# House_Illumination_Core.net
KiCad netlist of a schematic drawn in EAGLE
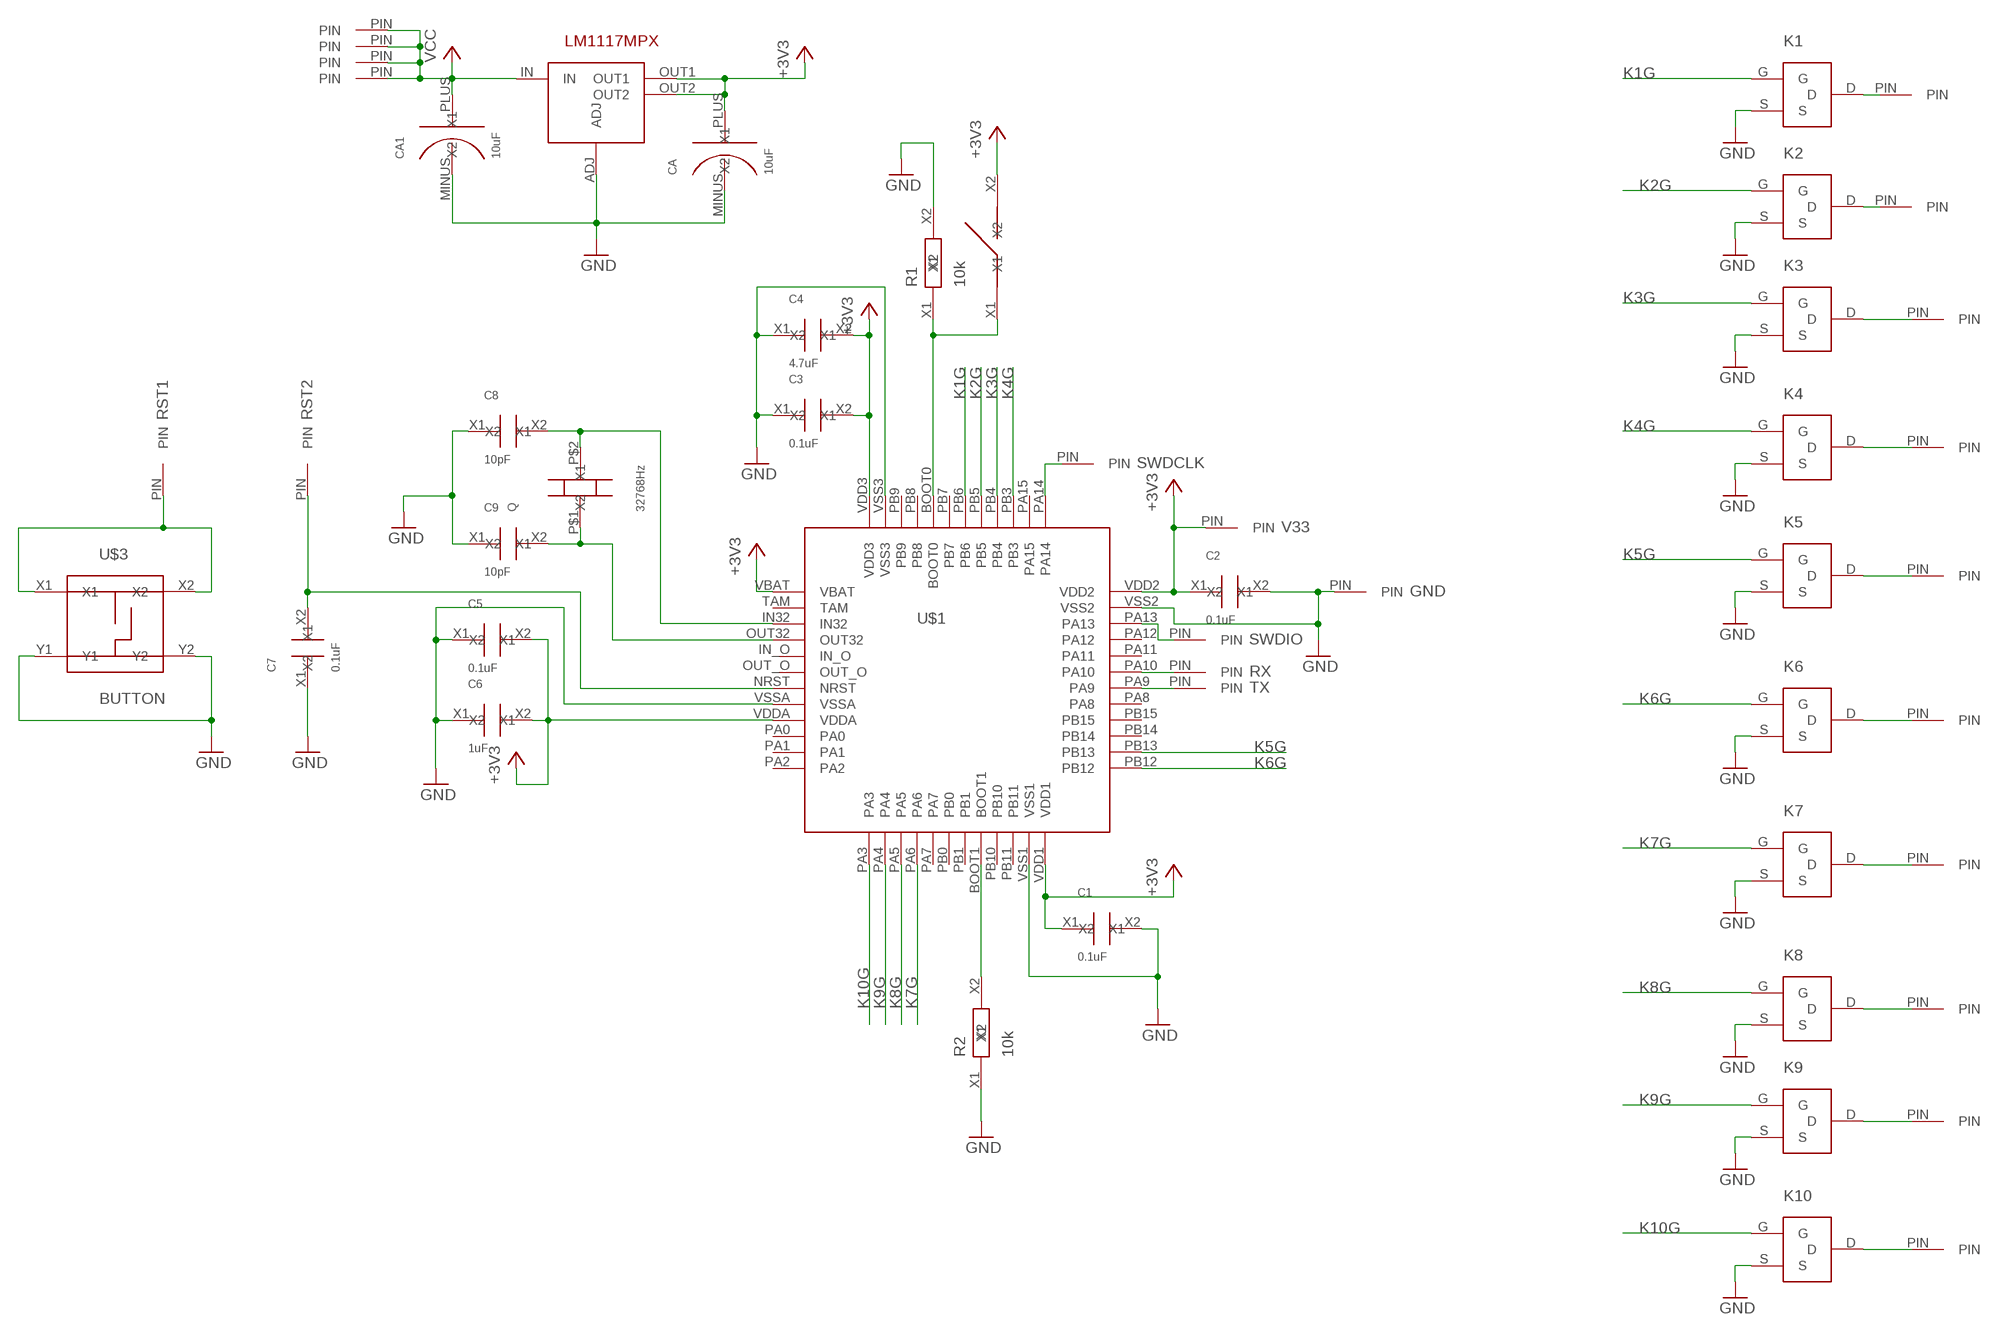
[diagram p0: schematic, sheet 1]

(export (version "E")
  (design (tool "Eeschema 10.0.6"))
  (components
    (comp (ref "C1")
      (value "0.1uF")
      (footprint "eagle-import:SMD_2.1X1.25")
      (libsource (lib "eagle-import") (part "C_SMD_2.1X1.25"))
    )
    (comp (ref "C2")
      (value "0.1uF")
      (footprint "eagle-import:SMD_2.1X1.25")
      (libsource (lib "eagle-import") (part "C_SMD_2.1X1.25"))
    )
    (comp (ref "C3")
      (value "0.1uF")
      (footprint "eagle-import:SMD_2.1X1.25")
      (libsource (lib "eagle-import") (part "C_SMD_2.1X1.25"))
    )
    (comp (ref "C4")
      (value "4.7uF")
      (footprint "eagle-import:SMD_2.1X1.25")
      (libsource (lib "eagle-import") (part "C_SMD_2.1X1.25"))
    )
    (comp (ref "C5")
      (value "0.1uF")
      (footprint "eagle-import:SMD_2.1X1.25")
      (libsource (lib "eagle-import") (part "C_SMD_2.1X1.25"))
    )
    (comp (ref "C6")
      (value "1uF")
      (footprint "eagle-import:SMD_2.1X1.25")
      (libsource (lib "eagle-import") (part "C_SMD_2.1X1.25"))
    )
    (comp (ref "C7")
      (value "0.1uF")
      (footprint "eagle-import:SMD_2.1X1.25")
      (libsource (lib "eagle-import") (part "C_SMD_2.1X1.25"))
    )
    (comp (ref "C8")
      (value "10pF")
      (footprint "eagle-import:SMD_2.1X1.25")
      (libsource (lib "eagle-import") (part "C_SMD_2.1X1.25"))
    )
    (comp (ref "C9")
      (value "10pF")
      (footprint "eagle-import:SMD_2.1X1.25")
      (libsource (lib "eagle-import") (part "C_SMD_2.1X1.25"))
    )
    (comp (ref "CA")
      (value "10uF")
      (footprint "eagle-import:C_SMD_TA_A")
      (libsource (lib "eagle-import") (part "C_SMD_TA_A"))
    )
    (comp (ref "CA1")
      (value "10uF")
      (footprint "eagle-import:C_SMD_TA_A")
      (libsource (lib "eagle-import") (part "C_SMD_TA_A"))
    )
    (comp (ref "GND")
      (value "PIN")
      (footprint "eagle-import:PIN")
      (libsource (lib "eagle-import") (part "PIN"))
    )
    (comp (ref "K1")
      (value "IRFML8244TRPBF")
      (footprint "eagle-import:IRFML8244TRPBF")
      (libsource (lib "eagle-import") (part "IRFML8244TRPBF"))
    )
    (comp (ref "K2")
      (value "IRFML8244TRPBF")
      (footprint "eagle-import:IRFML8244TRPBF")
      (libsource (lib "eagle-import") (part "IRFML8244TRPBF"))
    )
    (comp (ref "K3")
      (value "IRFML8244TRPBF")
      (footprint "eagle-import:IRFML8244TRPBF")
      (libsource (lib "eagle-import") (part "IRFML8244TRPBF"))
    )
    (comp (ref "K4")
      (value "IRFML8244TRPBF")
      (footprint "eagle-import:IRFML8244TRPBF")
      (libsource (lib "eagle-import") (part "IRFML8244TRPBF"))
    )
    (comp (ref "K5")
      (value "IRFML8244TRPBF")
      (footprint "eagle-import:IRFML8244TRPBF")
      (libsource (lib "eagle-import") (part "IRFML8244TRPBF"))
    )
    (comp (ref "K6")
      (value "IRFML8244TRPBF")
      (footprint "eagle-import:IRFML8244TRPBF")
      (libsource (lib "eagle-import") (part "IRFML8244TRPBF"))
    )
    (comp (ref "K7")
      (value "IRFML8244TRPBF")
      (footprint "eagle-import:IRFML8244TRPBF")
      (libsource (lib "eagle-import") (part "IRFML8244TRPBF"))
    )
    (comp (ref "K8")
      (value "IRFML8244TRPBF")
      (footprint "eagle-import:IRFML8244TRPBF")
      (libsource (lib "eagle-import") (part "IRFML8244TRPBF"))
    )
    (comp (ref "K9")
      (value "IRFML8244TRPBF")
      (footprint "eagle-import:IRFML8244TRPBF")
      (libsource (lib "eagle-import") (part "IRFML8244TRPBF"))
    )
    (comp (ref "K10")
      (value "IRFML8244TRPBF")
      (footprint "eagle-import:IRFML8244TRPBF")
      (libsource (lib "eagle-import") (part "IRFML8244TRPBF"))
    )
    (comp (ref "LED1")
      (value "PIN_1")
      (footprint "eagle-import:PIN_1")
      (libsource (lib "eagle-import") (part "PIN_1"))
    )
    (comp (ref "LED2")
      (value "PIN_1")
      (footprint "eagle-import:PIN_1")
      (libsource (lib "eagle-import") (part "PIN_1"))
    )
    (comp (ref "LED3")
      (value "PIN_1")
      (footprint "eagle-import:PIN_1")
      (libsource (lib "eagle-import") (part "PIN_1"))
    )
    (comp (ref "LED4")
      (value "PIN_1")
      (footprint "eagle-import:PIN_1")
      (libsource (lib "eagle-import") (part "PIN_1"))
    )
    (comp (ref "LED5")
      (value "PIN_1")
      (footprint "eagle-import:PIN_1")
      (libsource (lib "eagle-import") (part "PIN_1"))
    )
    (comp (ref "LED6")
      (value "PIN_1")
      (footprint "eagle-import:PIN_1")
      (libsource (lib "eagle-import") (part "PIN_1"))
    )
    (comp (ref "LED7")
      (value "PIN_1")
      (footprint "eagle-import:PIN_1")
      (libsource (lib "eagle-import") (part "PIN_1"))
    )
    (comp (ref "LED8")
      (value "PIN_1")
      (footprint "eagle-import:PIN_1")
      (libsource (lib "eagle-import") (part "PIN_1"))
    )
    (comp (ref "LED9")
      (value "PIN_1")
      (footprint "eagle-import:PIN_1")
      (libsource (lib "eagle-import") (part "PIN_1"))
    )
    (comp (ref "LED10")
      (value "PIN_1")
      (footprint "eagle-import:PIN_1")
      (libsource (lib "eagle-import") (part "PIN_1"))
    )
    (comp (ref "Q")
      (value "32768Hz")
      (footprint "eagle-import:QUARTZ_CYL")
      (libsource (lib "eagle-import") (part "QUARTZ_CYL"))
    )
    (comp (ref "R1")
      (value "10k")
      (footprint "eagle-import:SMD_2.1X1.25")
      (libsource (lib "eagle-import") (part "R_SMD_2.1X1.25"))
    )
    (comp (ref "R2")
      (value "10k")
      (footprint "eagle-import:SMD_2.1X1.25")
      (libsource (lib "eagle-import") (part "R_SMD_2.1X1.25"))
    )
    (comp (ref "RST1")
      (value "PIN")
      (footprint "eagle-import:PIN")
      (libsource (lib "eagle-import") (part "PIN"))
    )
    (comp (ref "RST2")
      (value "PIN")
      (footprint "eagle-import:PIN")
      (libsource (lib "eagle-import") (part "PIN"))
    )
    (comp (ref "RX")
      (value "PIN")
      (footprint "eagle-import:PIN")
      (libsource (lib "eagle-import") (part "PIN"))
    )
    (comp (ref "SWDCLK")
      (value "PIN")
      (footprint "eagle-import:PIN")
      (libsource (lib "eagle-import") (part "PIN"))
    )
    (comp (ref "SWDIO")
      (value "PIN")
      (footprint "eagle-import:PIN")
      (libsource (lib "eagle-import") (part "PIN"))
    )
    (comp (ref "TX")
      (value "PIN")
      (footprint "eagle-import:PIN")
      (libsource (lib "eagle-import") (part "PIN"))
    )
    (comp (ref "U$1")
      (value "STM32F103CBT6")
      (footprint "eagle-import:STM32F103CBT6")
      (libsource (lib "eagle-import") (part "STM32F103CBT6"))
    )
    (comp (ref "U$2")
      (value "DIP_1")
      (footprint "eagle-import:DIP_1")
      (libsource (lib "eagle-import") (part "DIP_1"))
    )
    (comp (ref "U$3")
      (value "BUTTON")
      (footprint "eagle-import:BUTTON")
      (libsource (lib "eagle-import") (part "BUTTON"))
    )
    (comp (ref "U$13")
      (value "LM1117MPX-ADJ")
      (footprint "eagle-import:LM1117MPX-ADJ")
      (libsource (lib "eagle-import") (part "LM1117MPX-ADJ"))
    )
    (comp (ref "V33")
      (value "PIN")
      (footprint "eagle-import:PIN")
      (libsource (lib "eagle-import") (part "PIN"))
    )
    (comp (ref "VCCPIN")
      (value "PIN_1")
      (footprint "eagle-import:PIN_1")
      (libsource (lib "eagle-import") (part "PIN_1"))
    )
    (comp (ref "VCCPIN1")
      (value "PIN_1")
      (footprint "eagle-import:PIN_1")
      (libsource (lib "eagle-import") (part "PIN_1"))
    )
    (comp (ref "VCCPIN2")
      (value "PIN_1")
      (footprint "eagle-import:PIN_1")
      (libsource (lib "eagle-import") (part "PIN_1"))
    )
    (comp (ref "VCCPIN3")
      (value "PIN_1")
      (footprint "eagle-import:PIN_1")
      (libsource (lib "eagle-import") (part "PIN_1"))
    )
  )
  (nets
    (net (code "1") (name "+3V3") (class "Default")
      (node (ref "C1") (pin "X1") (pinfunction "X1_X1") (pintype "bidirectional"))
      (node (ref "C2") (pin "X1") (pinfunction "X1_X1") (pintype "bidirectional"))
      (node (ref "C3") (pin "X2") (pinfunction "X2_X2") (pintype "bidirectional"))
      (node (ref "C4") (pin "X2") (pinfunction "X2_X2") (pintype "bidirectional"))
      (node (ref "C5") (pin "X2") (pinfunction "X2_X2") (pintype "bidirectional"))
      (node (ref "C6") (pin "X2") (pinfunction "X2_X2") (pintype "bidirectional"))
      (node (ref "CA") (pin "PLUS") (pinfunction "X2_PLUS") (pintype "bidirectional"))
      (node (ref "U$1") (pin "VBAT") (pinfunction "VBAT_VBAT") (pintype "bidirectional"))
      (node (ref "U$1") (pin "VDD1") (pinfunction "VDD1_VDD1") (pintype "bidirectional"))
      (node (ref "U$1") (pin "VDD2") (pinfunction "VDD2_VDD2") (pintype "bidirectional"))
      (node (ref "U$1") (pin "VDD3") (pinfunction "VDD3_VDD3") (pintype "bidirectional"))
      (node (ref "U$1") (pin "VDDA") (pinfunction "VDDA_VDDA") (pintype "bidirectional"))
      (node (ref "U$13") (pin "OUT1") (pinfunction "OUT1_OUT1") (pintype "bidirectional"))
      (node (ref "U$13") (pin "OUT2") (pinfunction "OUT2_OUT2") (pintype "bidirectional"))
      (node (ref "U$2") (pin "X2") (pinfunction "X2_X2") (pintype "bidirectional"))
      (node (ref "V33") (pin "PIN") (pinfunction "PIN_PIN") (pintype "bidirectional"))
    )
    (net (code "2") (name "/K1G") (class "Default")
      (node (ref "K1") (pin "G") (pinfunction "G_G") (pintype "bidirectional"))
      (node (ref "U$1") (pin "PB6") (pinfunction "PB6_PB6") (pintype "bidirectional"))
    )
    (net (code "3") (name "/K2G") (class "Default")
      (node (ref "K2") (pin "G") (pinfunction "G_G") (pintype "bidirectional"))
      (node (ref "U$1") (pin "PB5") (pinfunction "PB5_PB5") (pintype "bidirectional"))
    )
    (net (code "4") (name "/K3G") (class "Default")
      (node (ref "K3") (pin "G") (pinfunction "G_G") (pintype "bidirectional"))
      (node (ref "U$1") (pin "PB4") (pinfunction "PB4_PB4") (pintype "bidirectional"))
    )
    (net (code "5") (name "/K4G") (class "Default")
      (node (ref "K4") (pin "G") (pinfunction "G_G") (pintype "bidirectional"))
      (node (ref "U$1") (pin "PB3") (pinfunction "PB3_PB3") (pintype "bidirectional"))
    )
    (net (code "6") (name "/K5G") (class "Default")
      (node (ref "K5") (pin "G") (pinfunction "G_G") (pintype "bidirectional"))
      (node (ref "U$1") (pin "PB13") (pinfunction "PB13_PB13") (pintype "bidirectional"))
    )
    (net (code "7") (name "/K6G") (class "Default")
      (node (ref "K6") (pin "G") (pinfunction "G_G") (pintype "bidirectional"))
      (node (ref "U$1") (pin "PB12") (pinfunction "PB12_PB12") (pintype "bidirectional"))
    )
    (net (code "8") (name "/K7G") (class "Default")
      (node (ref "K7") (pin "G") (pinfunction "G_G") (pintype "bidirectional"))
      (node (ref "U$1") (pin "PA6") (pinfunction "PA6_PA6") (pintype "bidirectional"))
    )
    (net (code "9") (name "/K8G") (class "Default")
      (node (ref "K8") (pin "G") (pinfunction "G_G") (pintype "bidirectional"))
      (node (ref "U$1") (pin "PA5") (pinfunction "PA5_PA5") (pintype "bidirectional"))
    )
    (net (code "10") (name "/K9G") (class "Default")
      (node (ref "K9") (pin "G") (pinfunction "G_G") (pintype "bidirectional"))
      (node (ref "U$1") (pin "PA4") (pinfunction "PA4_PA4") (pintype "bidirectional"))
    )
    (net (code "11") (name "/K10G") (class "Default")
      (node (ref "K10") (pin "G") (pinfunction "G_G") (pintype "bidirectional"))
      (node (ref "U$1") (pin "PA3") (pinfunction "PA3_PA3") (pintype "bidirectional"))
    )
    (net (code "12") (name "GND") (class "Default")
      (node (ref "C1") (pin "X2") (pinfunction "X2_X2") (pintype "bidirectional"))
      (node (ref "C2") (pin "X2") (pinfunction "X2_X2") (pintype "bidirectional"))
      (node (ref "C3") (pin "X1") (pinfunction "X1_X1") (pintype "bidirectional"))
      (node (ref "C4") (pin "X1") (pinfunction "X1_X1") (pintype "bidirectional"))
      (node (ref "C5") (pin "X1") (pinfunction "X1_X1") (pintype "bidirectional"))
      (node (ref "C6") (pin "X1") (pinfunction "X1_X1") (pintype "bidirectional"))
      (node (ref "C7") (pin "X1") (pinfunction "X1_X1") (pintype "bidirectional"))
      (node (ref "C8") (pin "X1") (pinfunction "X1_X1") (pintype "bidirectional"))
      (node (ref "C9") (pin "X1") (pinfunction "X1_X1") (pintype "bidirectional"))
      (node (ref "CA") (pin "MINUS") (pinfunction "X1_MINUS") (pintype "bidirectional"))
      (node (ref "CA1") (pin "MINUS") (pinfunction "X1_MINUS") (pintype "bidirectional"))
      (node (ref "GND") (pin "PIN") (pinfunction "PIN_PIN") (pintype "bidirectional"))
      (node (ref "K1") (pin "S") (pinfunction "S_S") (pintype "bidirectional"))
      (node (ref "K10") (pin "S") (pinfunction "S_S") (pintype "bidirectional"))
      (node (ref "K2") (pin "S") (pinfunction "S_S") (pintype "bidirectional"))
      (node (ref "K3") (pin "S") (pinfunction "S_S") (pintype "bidirectional"))
      (node (ref "K4") (pin "S") (pinfunction "S_S") (pintype "bidirectional"))
      (node (ref "K5") (pin "S") (pinfunction "S_S") (pintype "bidirectional"))
      (node (ref "K6") (pin "S") (pinfunction "S_S") (pintype "bidirectional"))
      (node (ref "K7") (pin "S") (pinfunction "S_S") (pintype "bidirectional"))
      (node (ref "K8") (pin "S") (pinfunction "S_S") (pintype "bidirectional"))
      (node (ref "K9") (pin "S") (pinfunction "S_S") (pintype "bidirectional"))
      (node (ref "R1") (pin "X2") (pinfunction "X2_X2") (pintype "bidirectional"))
      (node (ref "R2") (pin "X1") (pinfunction "X1_X1") (pintype "bidirectional"))
      (node (ref "U$1") (pin "VSS1") (pinfunction "VSS1_VSS1") (pintype "bidirectional"))
      (node (ref "U$1") (pin "VSS2") (pinfunction "VSS2_VSS2") (pintype "bidirectional"))
      (node (ref "U$1") (pin "VSS3") (pinfunction "VSS3_VSS3") (pintype "bidirectional"))
      (node (ref "U$1") (pin "VSSA") (pinfunction "VSSA_VSSA") (pintype "bidirectional"))
      (node (ref "U$13") (pin "ADJ") (pinfunction "ADJ_ADJ") (pintype "bidirectional"))
      (node (ref "U$3") (pin "Y1") (pinfunction "Y1_Y1") (pintype "bidirectional"))
      (node (ref "U$3") (pin "Y2") (pinfunction "Y2_Y2") (pintype "bidirectional"))
    )
    (net (code "13") (name "Net-(C7-PadX2)") (class "Default")
      (node (ref "C7") (pin "X2") (pinfunction "X2_X2") (pintype "bidirectional"))
      (node (ref "RST2") (pin "PIN") (pinfunction "PIN_PIN") (pintype "bidirectional"))
      (node (ref "U$1") (pin "NRST") (pinfunction "NRST_NRST") (pintype "bidirectional"))
    )
    (net (code "14") (name "Net-(K1-PadD)") (class "Default")
      (node (ref "K1") (pin "D") (pinfunction "D_D") (pintype "bidirectional"))
      (node (ref "LED1") (pin "PIN") (pinfunction "PIN_PIN") (pintype "bidirectional"))
    )
    (net (code "15") (name "Net-(K2-PadD)") (class "Default")
      (node (ref "K2") (pin "D") (pinfunction "D_D") (pintype "bidirectional"))
      (node (ref "LED2") (pin "PIN") (pinfunction "PIN_PIN") (pintype "bidirectional"))
    )
    (net (code "16") (name "Net-(K3-PadD)") (class "Default")
      (node (ref "K3") (pin "D") (pinfunction "D_D") (pintype "bidirectional"))
      (node (ref "LED3") (pin "PIN") (pinfunction "PIN_PIN") (pintype "bidirectional"))
    )
    (net (code "17") (name "Net-(K4-PadD)") (class "Default")
      (node (ref "K4") (pin "D") (pinfunction "D_D") (pintype "bidirectional"))
      (node (ref "LED4") (pin "PIN") (pinfunction "PIN_PIN") (pintype "bidirectional"))
    )
    (net (code "18") (name "Net-(K5-PadD)") (class "Default")
      (node (ref "K5") (pin "D") (pinfunction "D_D") (pintype "bidirectional"))
      (node (ref "LED5") (pin "PIN") (pinfunction "PIN_PIN") (pintype "bidirectional"))
    )
    (net (code "19") (name "Net-(K6-PadD)") (class "Default")
      (node (ref "K6") (pin "D") (pinfunction "D_D") (pintype "bidirectional"))
      (node (ref "LED6") (pin "PIN") (pinfunction "PIN_PIN") (pintype "bidirectional"))
    )
    (net (code "20") (name "Net-(K7-PadD)") (class "Default")
      (node (ref "K7") (pin "D") (pinfunction "D_D") (pintype "bidirectional"))
      (node (ref "LED7") (pin "PIN") (pinfunction "PIN_PIN") (pintype "bidirectional"))
    )
    (net (code "21") (name "Net-(K8-PadD)") (class "Default")
      (node (ref "K8") (pin "D") (pinfunction "D_D") (pintype "bidirectional"))
      (node (ref "LED8") (pin "PIN") (pinfunction "PIN_PIN") (pintype "bidirectional"))
    )
    (net (code "22") (name "Net-(K9-PadD)") (class "Default")
      (node (ref "K9") (pin "D") (pinfunction "D_D") (pintype "bidirectional"))
      (node (ref "LED9") (pin "PIN") (pinfunction "PIN_PIN") (pintype "bidirectional"))
    )
    (net (code "23") (name "Net-(K10-PadD)") (class "Default")
      (node (ref "K10") (pin "D") (pinfunction "D_D") (pintype "bidirectional"))
      (node (ref "LED10") (pin "PIN") (pinfunction "PIN_PIN") (pintype "bidirectional"))
    )
    (net (code "24") (name "Net-(Q-X1)") (class "Default")
      (node (ref "C9") (pin "X2") (pinfunction "X2_X2") (pintype "bidirectional"))
      (node (ref "Q") (pin "P$1") (pinfunction "X1_P$1") (pintype "bidirectional"))
      (node (ref "U$1") (pin "OUT32") (pinfunction "OUT32_OUT32") (pintype "bidirectional"))
    )
    (net (code "25") (name "Net-(Q-X2)") (class "Default")
      (node (ref "C8") (pin "X2") (pinfunction "X2_X2") (pintype "bidirectional"))
      (node (ref "Q") (pin "P$2") (pinfunction "X2_P$2") (pintype "bidirectional"))
      (node (ref "U$1") (pin "IN32") (pinfunction "IN32_IN32") (pintype "bidirectional"))
    )
    (net (code "26") (name "Net-(R1-PadX1)") (class "Default")
      (node (ref "R1") (pin "X1") (pinfunction "X1_X1") (pintype "bidirectional"))
      (node (ref "U$1") (pin "BOOT0") (pinfunction "BOOT0_BOOT0") (pintype "bidirectional"))
      (node (ref "U$2") (pin "X1") (pinfunction "X1_X1") (pintype "bidirectional"))
    )
    (net (code "27") (name "Net-(R2-PadX2)") (class "Default")
      (node (ref "R2") (pin "X2") (pinfunction "X2_X2") (pintype "bidirectional"))
      (node (ref "U$1") (pin "BOOT1") (pinfunction "BOOT1_BOOT1") (pintype "bidirectional"))
    )
    (net (code "28") (name "Net-(RST1-PadPIN)") (class "Default")
      (node (ref "RST1") (pin "PIN") (pinfunction "PIN_PIN") (pintype "bidirectional"))
      (node (ref "U$3") (pin "X1") (pinfunction "X1_X1") (pintype "bidirectional"))
      (node (ref "U$3") (pin "X2") (pinfunction "X2_X2") (pintype "bidirectional"))
    )
    (net (code "29") (name "Net-(RX-PadPIN)") (class "Default")
      (node (ref "RX") (pin "PIN") (pinfunction "PIN_PIN") (pintype "bidirectional"))
      (node (ref "U$1") (pin "PA10") (pinfunction "PA10_PA10") (pintype "bidirectional"))
    )
    (net (code "30") (name "Net-(SWDCLK-PadPIN)") (class "Default")
      (node (ref "SWDCLK") (pin "PIN") (pinfunction "PIN_PIN") (pintype "bidirectional"))
      (node (ref "U$1") (pin "PA14") (pinfunction "PA14_PA14") (pintype "bidirectional"))
    )
    (net (code "31") (name "Net-(SWDIO-PadPIN)") (class "Default")
      (node (ref "SWDIO") (pin "PIN") (pinfunction "PIN_PIN") (pintype "bidirectional"))
      (node (ref "U$1") (pin "PA13") (pinfunction "PA13_PA13") (pintype "bidirectional"))
    )
    (net (code "32") (name "Net-(TX-PadPIN)") (class "Default")
      (node (ref "TX") (pin "PIN") (pinfunction "PIN_PIN") (pintype "bidirectional"))
      (node (ref "U$1") (pin "PA9") (pinfunction "PA9_PA9") (pintype "bidirectional"))
    )
    (net (code "33") (name "VCC") (class "Default")
      (node (ref "CA1") (pin "PLUS") (pinfunction "X2_PLUS") (pintype "bidirectional"))
      (node (ref "U$13") (pin "IN") (pinfunction "IN_IN") (pintype "bidirectional"))
      (node (ref "VCCPIN") (pin "PIN") (pinfunction "PIN_PIN") (pintype "bidirectional"))
      (node (ref "VCCPIN1") (pin "PIN") (pinfunction "PIN_PIN") (pintype "bidirectional"))
      (node (ref "VCCPIN2") (pin "PIN") (pinfunction "PIN_PIN") (pintype "bidirectional"))
      (node (ref "VCCPIN3") (pin "PIN") (pinfunction "PIN_PIN") (pintype "bidirectional"))
    )
    (net (code "34") (name "unconnected-(U$1-PadIN_O)") (class "Default")
      (node (ref "U$1") (pin "IN_O") (pinfunction "IN_O_IN_O") (pintype "bidirectional"))
    )
    (net (code "35") (name "unconnected-(U$1-PadOUT_O)") (class "Default")
      (node (ref "U$1") (pin "OUT_O") (pinfunction "OUT_O_OUT_O") (pintype "bidirectional"))
    )
    (net (code "36") (name "unconnected-(U$1-PadPA0)") (class "Default")
      (node (ref "U$1") (pin "PA0") (pinfunction "PA0_PA0") (pintype "bidirectional"))
    )
    (net (code "37") (name "unconnected-(U$1-PadPA1)") (class "Default")
      (node (ref "U$1") (pin "PA1") (pinfunction "PA1_PA1") (pintype "bidirectional"))
    )
    (net (code "38") (name "unconnected-(U$1-PadPA2)") (class "Default")
      (node (ref "U$1") (pin "PA2") (pinfunction "PA2_PA2") (pintype "bidirectional"))
    )
    (net (code "39") (name "unconnected-(U$1-PadPA7)") (class "Default")
      (node (ref "U$1") (pin "PA7") (pinfunction "PA7_PA7") (pintype "bidirectional"))
    )
    (net (code "40") (name "unconnected-(U$1-PadPA8)") (class "Default")
      (node (ref "U$1") (pin "PA8") (pinfunction "PA8_PA8") (pintype "bidirectional"))
    )
    (net (code "41") (name "unconnected-(U$1-PadPA11)") (class "Default")
      (node (ref "U$1") (pin "PA11") (pinfunction "PA11_PA11") (pintype "bidirectional"))
    )
    (net (code "42") (name "unconnected-(U$1-PadPA12)") (class "Default")
      (node (ref "U$1") (pin "PA12") (pinfunction "PA12_PA12") (pintype "bidirectional"))
    )
    (net (code "43") (name "unconnected-(U$1-PadPA15)") (class "Default")
      (node (ref "U$1") (pin "PA15") (pinfunction "PA15_PA15") (pintype "bidirectional"))
    )
    (net (code "44") (name "unconnected-(U$1-PadPB0)") (class "Default")
      (node (ref "U$1") (pin "PB0") (pinfunction "PB0_PB0") (pintype "bidirectional"))
    )
    (net (code "45") (name "unconnected-(U$1-PadPB1)") (class "Default")
      (node (ref "U$1") (pin "PB1") (pinfunction "PB1_PB1") (pintype "bidirectional"))
    )
    (net (code "46") (name "unconnected-(U$1-PadPB7)") (class "Default")
      (node (ref "U$1") (pin "PB7") (pinfunction "PB7_PB7") (pintype "bidirectional"))
    )
    (net (code "47") (name "unconnected-(U$1-PadPB8)") (class "Default")
      (node (ref "U$1") (pin "PB8") (pinfunction "PB8_PB8") (pintype "bidirectional"))
    )
    (net (code "48") (name "unconnected-(U$1-PadPB9)") (class "Default")
      (node (ref "U$1") (pin "PB9") (pinfunction "PB9_PB9") (pintype "bidirectional"))
    )
    (net (code "49") (name "unconnected-(U$1-PadPB10)") (class "Default")
      (node (ref "U$1") (pin "PB10") (pinfunction "PB10_PB10") (pintype "bidirectional"))
    )
    (net (code "50") (name "unconnected-(U$1-PadPB11)") (class "Default")
      (node (ref "U$1") (pin "PB11") (pinfunction "PB11_PB11") (pintype "bidirectional"))
    )
    (net (code "51") (name "unconnected-(U$1-PadPB14)") (class "Default")
      (node (ref "U$1") (pin "PB14") (pinfunction "PB14_PB14") (pintype "bidirectional"))
    )
    (net (code "52") (name "unconnected-(U$1-PadPB15)") (class "Default")
      (node (ref "U$1") (pin "PB15") (pinfunction "PB15_PB15") (pintype "bidirectional"))
    )
    (net (code "53") (name "unconnected-(U$1-PadTAM)") (class "Default")
      (node (ref "U$1") (pin "TAM") (pinfunction "TAM_TAM") (pintype "bidirectional"))
    )
  )
)
